# FPGA_Banks.net
KiCad netlist of a schematic drawn in Altium Designer
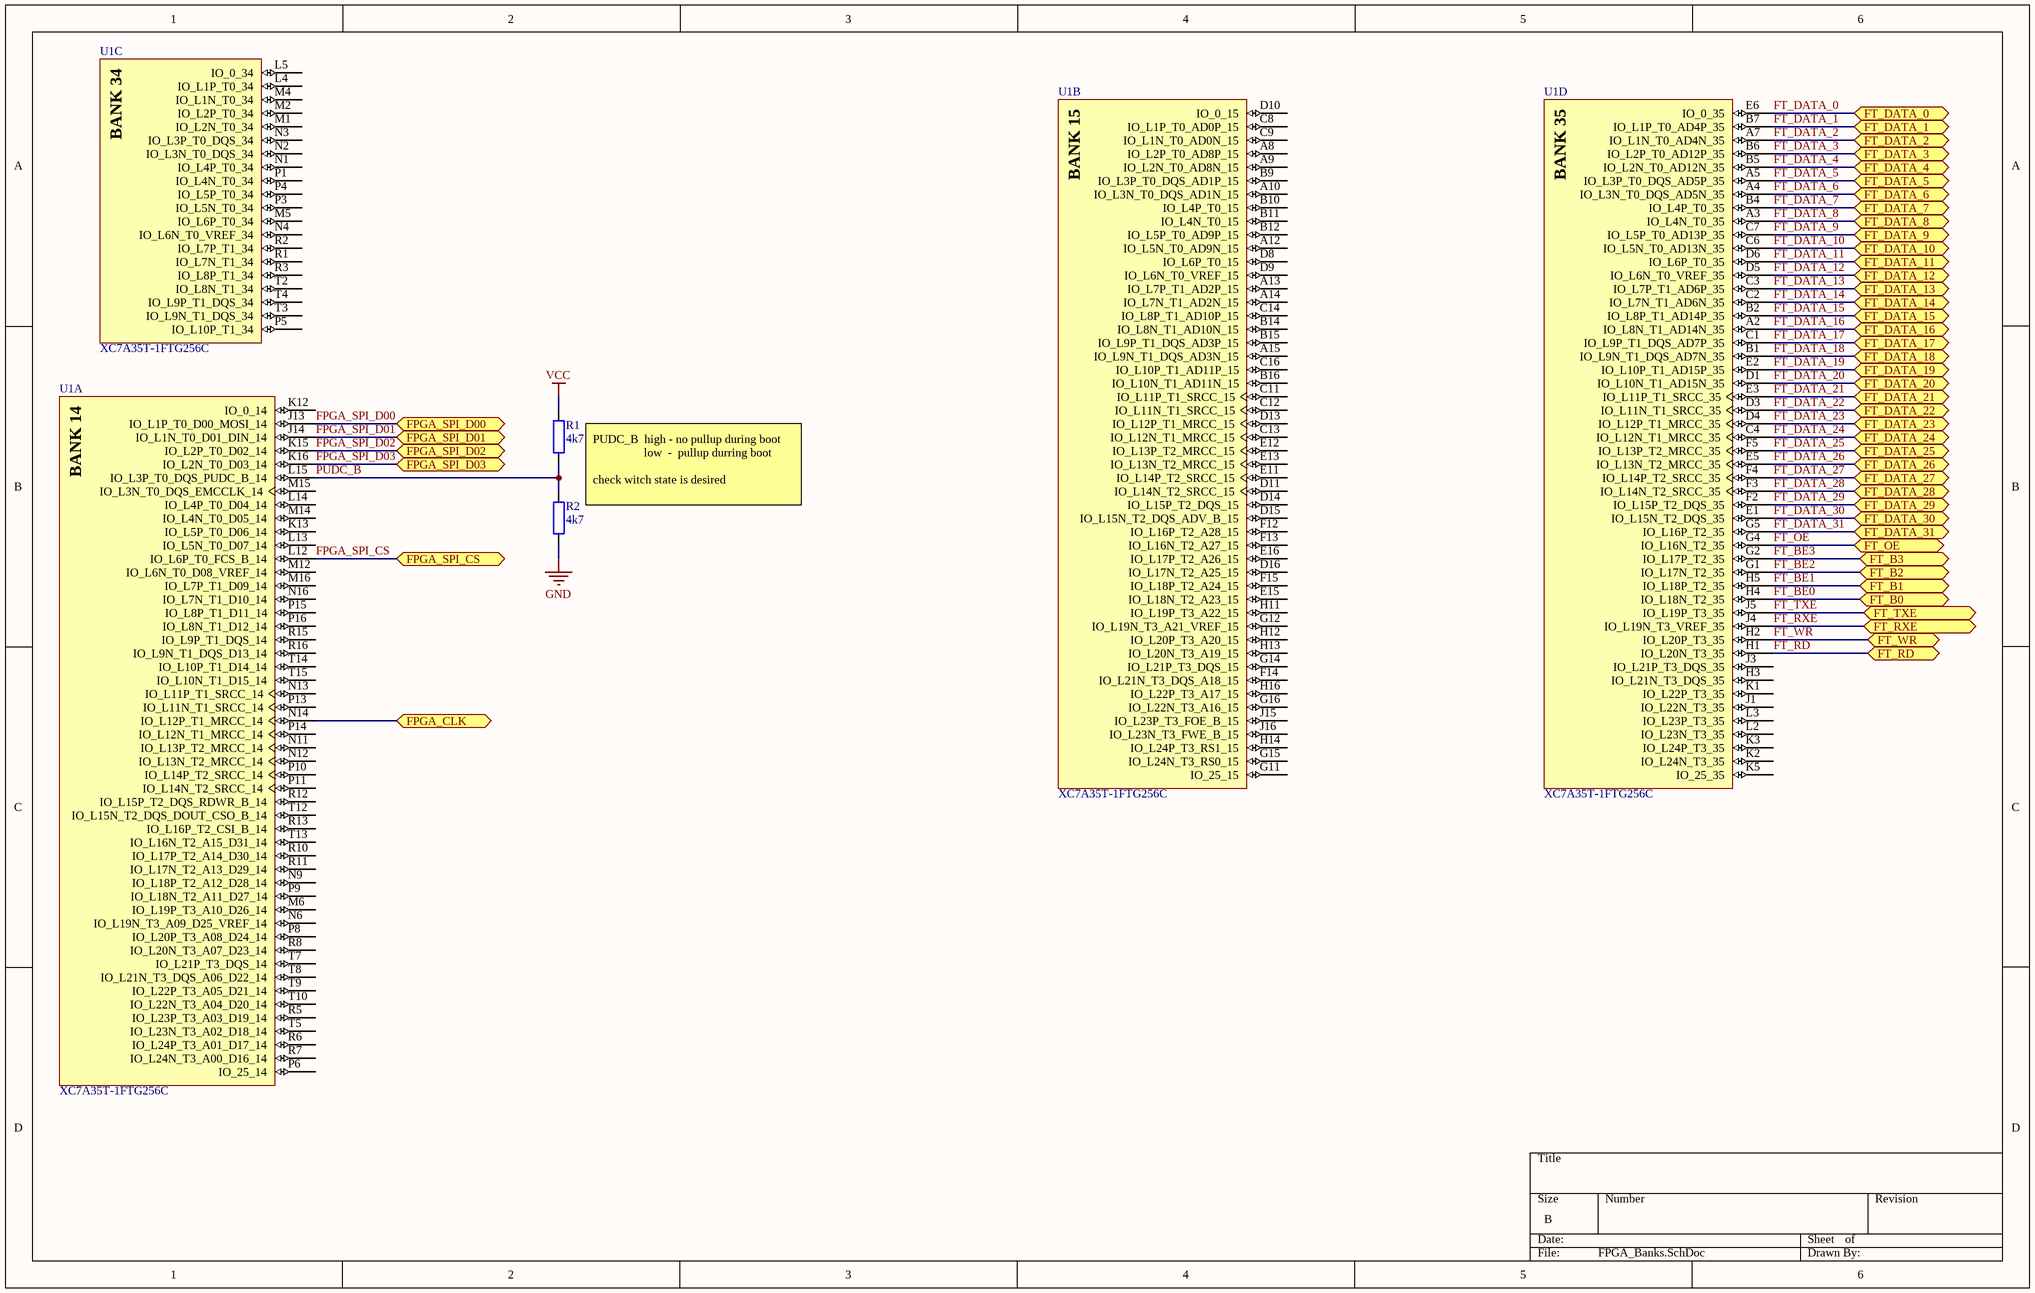
[diagram p0: FPGA_Banks.SchDoc]

(export (version "E")
  (design (tool "Eeschema 10.0.6"))
  (components
    (comp (ref "R1")
      (value "4k7")
      (footprint "RES0402")
      (libsource (lib "LimeMicroAltiumLib_schLib") (part "Res_0402"))
    )
    (comp (ref "R2")
      (value "4k7")
      (footprint "RES0402")
      (libsource (lib "LimeMicroAltiumLib_schLib") (part "Res_0402"))
    )
    (comp (ref "U1")
      (value "XC7A35T-1FTG256C")
      (footprint "FTG256")
      (description "Artix-7 FPGA, 170 User I/Os, 0 GTP, 256-Ball BGA, Speed Grade 1, Commercial Grade, Pb-Free")
      (fields (field (name "MANUFACTURER") "Xilinx"))
      (libsource (lib "Xilinx Artix-7") (part "XC7A35T-1FTG256C"))
    )
  )
  (nets
    (net (code "1") (name "/FPGA_CLK") (class "Default")
      (node (ref "U1") (pin "N14") (pinfunction "IO_L12P_T1_MRCC_14_N14") (pintype "bidirectional"))
    )
    (net (code "2") (name "/FPGA_SPI_CS") (class "Default")
      (node (ref "U1") (pin "L12") (pinfunction "IO_L6P_T0_FCS_B_14_L12") (pintype "bidirectional"))
    )
    (net (code "3") (name "/FPGA_SPI_D00") (class "Default")
      (node (ref "U1") (pin "J13") (pinfunction "IO_L1P_T0_D00_MOSI_14_J13") (pintype "bidirectional"))
    )
    (net (code "4") (name "/FPGA_SPI_D01") (class "Default")
      (node (ref "U1") (pin "J14") (pinfunction "IO_L1N_T0_D01_DIN_14_J14") (pintype "bidirectional"))
    )
    (net (code "5") (name "/FPGA_SPI_D02") (class "Default")
      (node (ref "U1") (pin "K15") (pinfunction "IO_L2P_T0_D02_14_K15") (pintype "bidirectional"))
    )
    (net (code "6") (name "/FPGA_SPI_D03") (class "Default")
      (node (ref "U1") (pin "K16") (pinfunction "IO_L2N_T0_D03_14_K16") (pintype "bidirectional"))
    )
    (net (code "7") (name "/FT_BE0") (class "Default")
      (node (ref "U1") (pin "H4") (pinfunction "IO_L18N_T2_35_H4") (pintype "bidirectional"))
    )
    (net (code "8") (name "/FT_BE1") (class "Default")
      (node (ref "U1") (pin "H5") (pinfunction "IO_L18P_T2_35_H5") (pintype "bidirectional"))
    )
    (net (code "9") (name "/FT_BE2") (class "Default")
      (node (ref "U1") (pin "G1") (pinfunction "IO_L17N_T2_35_G1") (pintype "bidirectional"))
    )
    (net (code "10") (name "/FT_BE3") (class "Default")
      (node (ref "U1") (pin "G2") (pinfunction "IO_L17P_T2_35_G2") (pintype "bidirectional"))
    )
    (net (code "11") (name "/FT_DATA_0") (class "Default")
      (node (ref "U1") (pin "E6") (pinfunction "IO_0_35_E6") (pintype "bidirectional"))
    )
    (net (code "12") (name "/FT_DATA_1") (class "Default")
      (node (ref "U1") (pin "B7") (pinfunction "IO_L1P_T0_AD4P_35_B7") (pintype "bidirectional"))
    )
    (net (code "13") (name "/FT_DATA_2") (class "Default")
      (node (ref "U1") (pin "A7") (pinfunction "IO_L1N_T0_AD4N_35_A7") (pintype "bidirectional"))
    )
    (net (code "14") (name "/FT_DATA_3") (class "Default")
      (node (ref "U1") (pin "B6") (pinfunction "IO_L2P_T0_AD12P_35_B6") (pintype "bidirectional"))
    )
    (net (code "15") (name "/FT_DATA_4") (class "Default")
      (node (ref "U1") (pin "B5") (pinfunction "IO_L2N_T0_AD12N_35_B5") (pintype "bidirectional"))
    )
    (net (code "16") (name "/FT_DATA_5") (class "Default")
      (node (ref "U1") (pin "A5") (pinfunction "IO_L3P_T0_DQS_AD5P_35_A5") (pintype "bidirectional"))
    )
    (net (code "17") (name "/FT_DATA_6") (class "Default")
      (node (ref "U1") (pin "A4") (pinfunction "IO_L3N_T0_DQS_AD5N_35_A4") (pintype "bidirectional"))
    )
    (net (code "18") (name "/FT_DATA_7") (class "Default")
      (node (ref "U1") (pin "B4") (pinfunction "IO_L4P_T0_35_B4") (pintype "bidirectional"))
    )
    (net (code "19") (name "/FT_DATA_8") (class "Default")
      (node (ref "U1") (pin "A3") (pinfunction "IO_L4N_T0_35_A3") (pintype "bidirectional"))
    )
    (net (code "20") (name "/FT_DATA_9") (class "Default")
      (node (ref "U1") (pin "C7") (pinfunction "IO_L5P_T0_AD13P_35_C7") (pintype "bidirectional"))
    )
    (net (code "21") (name "/FT_DATA_10") (class "Default")
      (node (ref "U1") (pin "C6") (pinfunction "IO_L5N_T0_AD13N_35_C6") (pintype "bidirectional"))
    )
    (net (code "22") (name "/FT_DATA_11") (class "Default")
      (node (ref "U1") (pin "D6") (pinfunction "IO_L6P_T0_35_D6") (pintype "bidirectional"))
    )
    (net (code "23") (name "/FT_DATA_12") (class "Default")
      (node (ref "U1") (pin "D5") (pinfunction "IO_L6N_T0_VREF_35_D5") (pintype "bidirectional"))
    )
    (net (code "24") (name "/FT_DATA_13") (class "Default")
      (node (ref "U1") (pin "C3") (pinfunction "IO_L7P_T1_AD6P_35_C3") (pintype "bidirectional"))
    )
    (net (code "25") (name "/FT_DATA_14") (class "Default")
      (node (ref "U1") (pin "C2") (pinfunction "IO_L7N_T1_AD6N_35_C2") (pintype "bidirectional"))
    )
    (net (code "26") (name "/FT_DATA_15") (class "Default")
      (node (ref "U1") (pin "B2") (pinfunction "IO_L8P_T1_AD14P_35_B2") (pintype "bidirectional"))
    )
    (net (code "27") (name "/FT_DATA_16") (class "Default")
      (node (ref "U1") (pin "A2") (pinfunction "IO_L8N_T1_AD14N_35_A2") (pintype "bidirectional"))
    )
    (net (code "28") (name "/FT_DATA_17") (class "Default")
      (node (ref "U1") (pin "C1") (pinfunction "IO_L9P_T1_DQS_AD7P_35_C1") (pintype "bidirectional"))
    )
    (net (code "29") (name "/FT_DATA_18") (class "Default")
      (node (ref "U1") (pin "B1") (pinfunction "IO_L9N_T1_DQS_AD7N_35_B1") (pintype "bidirectional"))
    )
    (net (code "30") (name "/FT_DATA_19") (class "Default")
      (node (ref "U1") (pin "E2") (pinfunction "IO_L10P_T1_AD15P_35_E2") (pintype "bidirectional"))
    )
    (net (code "31") (name "/FT_DATA_20") (class "Default")
      (node (ref "U1") (pin "D1") (pinfunction "IO_L10N_T1_AD15N_35_D1") (pintype "bidirectional"))
    )
    (net (code "32") (name "/FT_DATA_21") (class "Default")
      (node (ref "U1") (pin "E3") (pinfunction "IO_L11P_T1_SRCC_35_E3") (pintype "bidirectional"))
    )
    (net (code "33") (name "/FT_DATA_22") (class "Default")
      (node (ref "U1") (pin "D3") (pinfunction "IO_L11N_T1_SRCC_35_D3") (pintype "bidirectional"))
    )
    (net (code "34") (name "/FT_DATA_23") (class "Default")
      (node (ref "U1") (pin "D4") (pinfunction "IO_L12P_T1_MRCC_35_D4") (pintype "bidirectional"))
    )
    (net (code "35") (name "/FT_DATA_24") (class "Default")
      (node (ref "U1") (pin "C4") (pinfunction "IO_L12N_T1_MRCC_35_C4") (pintype "bidirectional"))
    )
    (net (code "36") (name "/FT_DATA_25") (class "Default")
      (node (ref "U1") (pin "F5") (pinfunction "IO_L13P_T2_MRCC_35_F5") (pintype "bidirectional"))
    )
    (net (code "37") (name "/FT_DATA_26") (class "Default")
      (node (ref "U1") (pin "E5") (pinfunction "IO_L13N_T2_MRCC_35_E5") (pintype "bidirectional"))
    )
    (net (code "38") (name "/FT_DATA_27") (class "Default")
      (node (ref "U1") (pin "F4") (pinfunction "IO_L14P_T2_SRCC_35_F4") (pintype "bidirectional"))
    )
    (net (code "39") (name "/FT_DATA_28") (class "Default")
      (node (ref "U1") (pin "F3") (pinfunction "IO_L14N_T2_SRCC_35_F3") (pintype "bidirectional"))
    )
    (net (code "40") (name "/FT_DATA_29") (class "Default")
      (node (ref "U1") (pin "F2") (pinfunction "IO_L15P_T2_DQS_35_F2") (pintype "bidirectional"))
    )
    (net (code "41") (name "/FT_DATA_30") (class "Default")
      (node (ref "U1") (pin "E1") (pinfunction "IO_L15N_T2_DQS_35_E1") (pintype "bidirectional"))
    )
    (net (code "42") (name "/FT_DATA_31") (class "Default")
      (node (ref "U1") (pin "G5") (pinfunction "IO_L16P_T2_35_G5") (pintype "bidirectional"))
    )
    (net (code "43") (name "/FT_OE") (class "Default")
      (node (ref "U1") (pin "G4") (pinfunction "IO_L16N_T2_35_G4") (pintype "bidirectional"))
    )
    (net (code "44") (name "/FT_RD") (class "Default")
      (node (ref "U1") (pin "H1") (pinfunction "IO_L20N_T3_35_H1") (pintype "bidirectional"))
    )
    (net (code "45") (name "/FT_RXE") (class "Default")
      (node (ref "U1") (pin "J4") (pinfunction "IO_L19N_T3_VREF_35_J4") (pintype "bidirectional"))
    )
    (net (code "46") (name "/FT_TXE") (class "Default")
      (node (ref "U1") (pin "J5") (pinfunction "IO_L19P_T3_35_J5") (pintype "bidirectional"))
    )
    (net (code "47") (name "/FT_WR") (class "Default")
      (node (ref "U1") (pin "H2") (pinfunction "IO_L20P_T3_35_H2") (pintype "bidirectional"))
    )
    (net (code "48") (name "/PUDC_B") (class "Default")
      (node (ref "R1") (pin "2") (pinfunction "2_2") (pintype "passive"))
      (node (ref "R2") (pin "1") (pinfunction "1_1") (pintype "passive"))
      (node (ref "U1") (pin "L15") (pinfunction "IO_L3P_T0_DQS_PUDC_B_14_L15") (pintype "bidirectional"))
    )
    (net (code "49") (name "GND") (class "Default")
      (node (ref "R2") (pin "2") (pinfunction "2_2") (pintype "passive"))
    )
    (net (code "50") (name "VCC") (class "Default")
      (node (ref "R1") (pin "1") (pinfunction "1_1") (pintype "passive"))
    )
    (net (code "51") (name "unconnected-(U1A-IO_0_14-PadK12)") (class "Default")
      (node (ref "U1") (pin "K12") (pinfunction "IO_0_14_K12") (pintype "bidirectional"))
    )
    (net (code "52") (name "unconnected-(U1A-IO_25_14-PadP6)") (class "Default")
      (node (ref "U1") (pin "P6") (pinfunction "IO_25_14_P6") (pintype "bidirectional"))
    )
    (net (code "53") (name "unconnected-(U1A-IO_L3N_T0_DQS_EMCCLK_14-PadM15)") (class "Default")
      (node (ref "U1") (pin "M15") (pinfunction "IO_L3N_T0_DQS_EMCCLK_14_M15") (pintype "bidirectional"))
    )
    (net (code "54") (name "unconnected-(U1A-IO_L4N_T0_D05_14-PadM14)") (class "Default")
      (node (ref "U1") (pin "M14") (pinfunction "IO_L4N_T0_D05_14_M14") (pintype "bidirectional"))
    )
    (net (code "55") (name "unconnected-(U1A-IO_L4P_T0_D04_14-PadL14)") (class "Default")
      (node (ref "U1") (pin "L14") (pinfunction "IO_L4P_T0_D04_14_L14") (pintype "bidirectional"))
    )
    (net (code "56") (name "unconnected-(U1A-IO_L5N_T0_D07_14-PadL13)") (class "Default")
      (node (ref "U1") (pin "L13") (pinfunction "IO_L5N_T0_D07_14_L13") (pintype "bidirectional"))
    )
    (net (code "57") (name "unconnected-(U1A-IO_L5P_T0_D06_14-PadK13)") (class "Default")
      (node (ref "U1") (pin "K13") (pinfunction "IO_L5P_T0_D06_14_K13") (pintype "bidirectional"))
    )
    (net (code "58") (name "unconnected-(U1A-IO_L6N_T0_D08_VREF_14-PadM12)") (class "Default")
      (node (ref "U1") (pin "M12") (pinfunction "IO_L6N_T0_D08_VREF_14_M12") (pintype "bidirectional"))
    )
    (net (code "59") (name "unconnected-(U1A-IO_L7N_T1_D10_14-PadN16)") (class "Default")
      (node (ref "U1") (pin "N16") (pinfunction "IO_L7N_T1_D10_14_N16") (pintype "bidirectional"))
    )
    (net (code "60") (name "unconnected-(U1A-IO_L7P_T1_D09_14-PadM16)") (class "Default")
      (node (ref "U1") (pin "M16") (pinfunction "IO_L7P_T1_D09_14_M16") (pintype "bidirectional"))
    )
    (net (code "61") (name "unconnected-(U1A-IO_L8N_T1_D12_14-PadP16)") (class "Default")
      (node (ref "U1") (pin "P16") (pinfunction "IO_L8N_T1_D12_14_P16") (pintype "bidirectional"))
    )
    (net (code "62") (name "unconnected-(U1A-IO_L8P_T1_D11_14-PadP15)") (class "Default")
      (node (ref "U1") (pin "P15") (pinfunction "IO_L8P_T1_D11_14_P15") (pintype "bidirectional"))
    )
    (net (code "63") (name "unconnected-(U1A-IO_L9N_T1_DQS_D13_14-PadR16)") (class "Default")
      (node (ref "U1") (pin "R16") (pinfunction "IO_L9N_T1_DQS_D13_14_R16") (pintype "bidirectional"))
    )
    (net (code "64") (name "unconnected-(U1A-IO_L9P_T1_DQS_14-PadR15)") (class "Default")
      (node (ref "U1") (pin "R15") (pinfunction "IO_L9P_T1_DQS_14_R15") (pintype "bidirectional"))
    )
    (net (code "65") (name "unconnected-(U1A-IO_L10N_T1_D15_14-PadT15)") (class "Default")
      (node (ref "U1") (pin "T15") (pinfunction "IO_L10N_T1_D15_14_T15") (pintype "bidirectional"))
    )
    (net (code "66") (name "unconnected-(U1A-IO_L10P_T1_D14_14-PadT14)") (class "Default")
      (node (ref "U1") (pin "T14") (pinfunction "IO_L10P_T1_D14_14_T14") (pintype "bidirectional"))
    )
    (net (code "67") (name "unconnected-(U1A-IO_L11N_T1_SRCC_14-PadP13)") (class "Default")
      (node (ref "U1") (pin "P13") (pinfunction "IO_L11N_T1_SRCC_14_P13") (pintype "bidirectional"))
    )
    (net (code "68") (name "unconnected-(U1A-IO_L11P_T1_SRCC_14-PadN13)") (class "Default")
      (node (ref "U1") (pin "N13") (pinfunction "IO_L11P_T1_SRCC_14_N13") (pintype "bidirectional"))
    )
    (net (code "69") (name "unconnected-(U1A-IO_L12N_T1_MRCC_14-PadP14)") (class "Default")
      (node (ref "U1") (pin "P14") (pinfunction "IO_L12N_T1_MRCC_14_P14") (pintype "bidirectional"))
    )
    (net (code "70") (name "unconnected-(U1A-IO_L13N_T2_MRCC_14-PadN12)") (class "Default")
      (node (ref "U1") (pin "N12") (pinfunction "IO_L13N_T2_MRCC_14_N12") (pintype "bidirectional"))
    )
    (net (code "71") (name "unconnected-(U1A-IO_L13P_T2_MRCC_14-PadN11)") (class "Default")
      (node (ref "U1") (pin "N11") (pinfunction "IO_L13P_T2_MRCC_14_N11") (pintype "bidirectional"))
    )
    (net (code "72") (name "unconnected-(U1A-IO_L14N_T2_SRCC_14-PadP11)") (class "Default")
      (node (ref "U1") (pin "P11") (pinfunction "IO_L14N_T2_SRCC_14_P11") (pintype "bidirectional"))
    )
    (net (code "73") (name "unconnected-(U1A-IO_L14P_T2_SRCC_14-PadP10)") (class "Default")
      (node (ref "U1") (pin "P10") (pinfunction "IO_L14P_T2_SRCC_14_P10") (pintype "bidirectional"))
    )
    (net (code "74") (name "unconnected-(U1A-IO_L15N_T2_DQS_DOUT_CSO_B_14-PadT12)") (class "Default")
      (node (ref "U1") (pin "T12") (pinfunction "IO_L15N_T2_DQS_DOUT_CSO_B_14_T12") (pintype "bidirectional"))
    )
    (net (code "75") (name "unconnected-(U1A-IO_L15P_T2_DQS_RDWR_B_14-PadR12)") (class "Default")
      (node (ref "U1") (pin "R12") (pinfunction "IO_L15P_T2_DQS_RDWR_B_14_R12") (pintype "bidirectional"))
    )
    (net (code "76") (name "unconnected-(U1A-IO_L16N_T2_A15_D31_14-PadT13)") (class "Default")
      (node (ref "U1") (pin "T13") (pinfunction "IO_L16N_T2_A15_D31_14_T13") (pintype "bidirectional"))
    )
    (net (code "77") (name "unconnected-(U1A-IO_L16P_T2_CSI_B_14-PadR13)") (class "Default")
      (node (ref "U1") (pin "R13") (pinfunction "IO_L16P_T2_CSI_B_14_R13") (pintype "bidirectional"))
    )
    (net (code "78") (name "unconnected-(U1A-IO_L17N_T2_A13_D29_14-PadR11)") (class "Default")
      (node (ref "U1") (pin "R11") (pinfunction "IO_L17N_T2_A13_D29_14_R11") (pintype "bidirectional"))
    )
    (net (code "79") (name "unconnected-(U1A-IO_L17P_T2_A14_D30_14-PadR10)") (class "Default")
      (node (ref "U1") (pin "R10") (pinfunction "IO_L17P_T2_A14_D30_14_R10") (pintype "bidirectional"))
    )
    (net (code "80") (name "unconnected-(U1A-IO_L18N_T2_A11_D27_14-PadP9)") (class "Default")
      (node (ref "U1") (pin "P9") (pinfunction "IO_L18N_T2_A11_D27_14_P9") (pintype "bidirectional"))
    )
    (net (code "81") (name "unconnected-(U1A-IO_L18P_T2_A12_D28_14-PadN9)") (class "Default")
      (node (ref "U1") (pin "N9") (pinfunction "IO_L18P_T2_A12_D28_14_N9") (pintype "bidirectional"))
    )
    (net (code "82") (name "unconnected-(U1A-IO_L19N_T3_A09_D25_VREF_14-PadN6)") (class "Default")
      (node (ref "U1") (pin "N6") (pinfunction "IO_L19N_T3_A09_D25_VREF_14_N6") (pintype "bidirectional"))
    )
    (net (code "83") (name "unconnected-(U1A-IO_L19P_T3_A10_D26_14-PadM6)") (class "Default")
      (node (ref "U1") (pin "M6") (pinfunction "IO_L19P_T3_A10_D26_14_M6") (pintype "bidirectional"))
    )
    (net (code "84") (name "unconnected-(U1A-IO_L20N_T3_A07_D23_14-PadR8)") (class "Default")
      (node (ref "U1") (pin "R8") (pinfunction "IO_L20N_T3_A07_D23_14_R8") (pintype "bidirectional"))
    )
    (net (code "85") (name "unconnected-(U1A-IO_L20P_T3_A08_D24_14-PadP8)") (class "Default")
      (node (ref "U1") (pin "P8") (pinfunction "IO_L20P_T3_A08_D24_14_P8") (pintype "bidirectional"))
    )
    (net (code "86") (name "unconnected-(U1A-IO_L21N_T3_DQS_A06_D22_14-PadT8)") (class "Default")
      (node (ref "U1") (pin "T8") (pinfunction "IO_L21N_T3_DQS_A06_D22_14_T8") (pintype "bidirectional"))
    )
    (net (code "87") (name "unconnected-(U1A-IO_L21P_T3_DQS_14-PadT7)") (class "Default")
      (node (ref "U1") (pin "T7") (pinfunction "IO_L21P_T3_DQS_14_T7") (pintype "bidirectional"))
    )
    (net (code "88") (name "unconnected-(U1A-IO_L22N_T3_A04_D20_14-PadT10)") (class "Default")
      (node (ref "U1") (pin "T10") (pinfunction "IO_L22N_T3_A04_D20_14_T10") (pintype "bidirectional"))
    )
    (net (code "89") (name "unconnected-(U1A-IO_L22P_T3_A05_D21_14-PadT9)") (class "Default")
      (node (ref "U1") (pin "T9") (pinfunction "IO_L22P_T3_A05_D21_14_T9") (pintype "bidirectional"))
    )
    (net (code "90") (name "unconnected-(U1A-IO_L23N_T3_A02_D18_14-PadT5)") (class "Default")
      (node (ref "U1") (pin "T5") (pinfunction "IO_L23N_T3_A02_D18_14_T5") (pintype "bidirectional"))
    )
    (net (code "91") (name "unconnected-(U1A-IO_L23P_T3_A03_D19_14-PadR5)") (class "Default")
      (node (ref "U1") (pin "R5") (pinfunction "IO_L23P_T3_A03_D19_14_R5") (pintype "bidirectional"))
    )
    (net (code "92") (name "unconnected-(U1A-IO_L24N_T3_A00_D16_14-PadR7)") (class "Default")
      (node (ref "U1") (pin "R7") (pinfunction "IO_L24N_T3_A00_D16_14_R7") (pintype "bidirectional"))
    )
    (net (code "93") (name "unconnected-(U1A-IO_L24P_T3_A01_D17_14-PadR6)") (class "Default")
      (node (ref "U1") (pin "R6") (pinfunction "IO_L24P_T3_A01_D17_14_R6") (pintype "bidirectional"))
    )
    (net (code "94") (name "unconnected-(U1B-IO_0_15-PadD10)") (class "Default")
      (node (ref "U1") (pin "D10") (pinfunction "IO_0_15_D10") (pintype "bidirectional"))
    )
    (net (code "95") (name "unconnected-(U1B-IO_25_15-PadG11)") (class "Default")
      (node (ref "U1") (pin "G11") (pinfunction "IO_25_15_G11") (pintype "bidirectional"))
    )
    (net (code "96") (name "unconnected-(U1B-IO_L1N_T0_AD0N_15-PadC9)") (class "Default")
      (node (ref "U1") (pin "C9") (pinfunction "IO_L1N_T0_AD0N_15_C9") (pintype "bidirectional"))
    )
    (net (code "97") (name "unconnected-(U1B-IO_L1P_T0_AD0P_15-PadC8)") (class "Default")
      (node (ref "U1") (pin "C8") (pinfunction "IO_L1P_T0_AD0P_15_C8") (pintype "bidirectional"))
    )
    (net (code "98") (name "unconnected-(U1B-IO_L2N_T0_AD8N_15-PadA9)") (class "Default")
      (node (ref "U1") (pin "A9") (pinfunction "IO_L2N_T0_AD8N_15_A9") (pintype "bidirectional"))
    )
    (net (code "99") (name "unconnected-(U1B-IO_L2P_T0_AD8P_15-PadA8)") (class "Default")
      (node (ref "U1") (pin "A8") (pinfunction "IO_L2P_T0_AD8P_15_A8") (pintype "bidirectional"))
    )
    (net (code "100") (name "unconnected-(U1B-IO_L3N_T0_DQS_AD1N_15-PadA10)") (class "Default")
      (node (ref "U1") (pin "A10") (pinfunction "IO_L3N_T0_DQS_AD1N_15_A10") (pintype "bidirectional"))
    )
    (net (code "101") (name "unconnected-(U1B-IO_L3P_T0_DQS_AD1P_15-PadB9)") (class "Default")
      (node (ref "U1") (pin "B9") (pinfunction "IO_L3P_T0_DQS_AD1P_15_B9") (pintype "bidirectional"))
    )
    (net (code "102") (name "unconnected-(U1B-IO_L4N_T0_15-PadB11)") (class "Default")
      (node (ref "U1") (pin "B11") (pinfunction "IO_L4N_T0_15_B11") (pintype "bidirectional"))
    )
    (net (code "103") (name "unconnected-(U1B-IO_L4P_T0_15-PadB10)") (class "Default")
      (node (ref "U1") (pin "B10") (pinfunction "IO_L4P_T0_15_B10") (pintype "bidirectional"))
    )
    (net (code "104") (name "unconnected-(U1B-IO_L5N_T0_AD9N_15-PadA12)") (class "Default")
      (node (ref "U1") (pin "A12") (pinfunction "IO_L5N_T0_AD9N_15_A12") (pintype "bidirectional"))
    )
    (net (code "105") (name "unconnected-(U1B-IO_L5P_T0_AD9P_15-PadB12)") (class "Default")
      (node (ref "U1") (pin "B12") (pinfunction "IO_L5P_T0_AD9P_15_B12") (pintype "bidirectional"))
    )
    (net (code "106") (name "unconnected-(U1B-IO_L6N_T0_VREF_15-PadD9)") (class "Default")
      (node (ref "U1") (pin "D9") (pinfunction "IO_L6N_T0_VREF_15_D9") (pintype "bidirectional"))
    )
    (net (code "107") (name "unconnected-(U1B-IO_L6P_T0_15-PadD8)") (class "Default")
      (node (ref "U1") (pin "D8") (pinfunction "IO_L6P_T0_15_D8") (pintype "bidirectional"))
    )
    (net (code "108") (name "unconnected-(U1B-IO_L7N_T1_AD2N_15-PadA14)") (class "Default")
      (node (ref "U1") (pin "A14") (pinfunction "IO_L7N_T1_AD2N_15_A14") (pintype "bidirectional"))
    )
    (net (code "109") (name "unconnected-(U1B-IO_L7P_T1_AD2P_15-PadA13)") (class "Default")
      (node (ref "U1") (pin "A13") (pinfunction "IO_L7P_T1_AD2P_15_A13") (pintype "bidirectional"))
    )
    (net (code "110") (name "unconnected-(U1B-IO_L8N_T1_AD10N_15-PadB14)") (class "Default")
      (node (ref "U1") (pin "B14") (pinfunction "IO_L8N_T1_AD10N_15_B14") (pintype "bidirectional"))
    )
    (net (code "111") (name "unconnected-(U1B-IO_L8P_T1_AD10P_15-PadC14)") (class "Default")
      (node (ref "U1") (pin "C14") (pinfunction "IO_L8P_T1_AD10P_15_C14") (pintype "bidirectional"))
    )
    (net (code "112") (name "unconnected-(U1B-IO_L9N_T1_DQS_AD3N_15-PadA15)") (class "Default")
      (node (ref "U1") (pin "A15") (pinfunction "IO_L9N_T1_DQS_AD3N_15_A15") (pintype "bidirectional"))
    )
    (net (code "113") (name "unconnected-(U1B-IO_L9P_T1_DQS_AD3P_15-PadB15)") (class "Default")
      (node (ref "U1") (pin "B15") (pinfunction "IO_L9P_T1_DQS_AD3P_15_B15") (pintype "bidirectional"))
    )
    (net (code "114") (name "unconnected-(U1B-IO_L10N_T1_AD11N_15-PadB16)") (class "Default")
      (node (ref "U1") (pin "B16") (pinfunction "IO_L10N_T1_AD11N_15_B16") (pintype "bidirectional"))
    )
    (net (code "115") (name "unconnected-(U1B-IO_L10P_T1_AD11P_15-PadC16)") (class "Default")
      (node (ref "U1") (pin "C16") (pinfunction "IO_L10P_T1_AD11P_15_C16") (pintype "bidirectional"))
    )
    (net (code "116") (name "unconnected-(U1B-IO_L11N_T1_SRCC_15-PadC12)") (class "Default")
      (node (ref "U1") (pin "C12") (pinfunction "IO_L11N_T1_SRCC_15_C12") (pintype "bidirectional"))
    )
    (net (code "117") (name "unconnected-(U1B-IO_L11P_T1_SRCC_15-PadC11)") (class "Default")
      (node (ref "U1") (pin "C11") (pinfunction "IO_L11P_T1_SRCC_15_C11") (pintype "bidirectional"))
    )
    (net (code "118") (name "unconnected-(U1B-IO_L12N_T1_MRCC_15-PadC13)") (class "Default")
      (node (ref "U1") (pin "C13") (pinfunction "IO_L12N_T1_MRCC_15_C13") (pintype "bidirectional"))
    )
    (net (code "119") (name "unconnected-(U1B-IO_L12P_T1_MRCC_15-PadD13)") (class "Default")
      (node (ref "U1") (pin "D13") (pinfunction "IO_L12P_T1_MRCC_15_D13") (pintype "bidirectional"))
    )
    (net (code "120") (name "unconnected-(U1B-IO_L13N_T2_MRCC_15-PadE13)") (class "Default")
      (node (ref "U1") (pin "E13") (pinfunction "IO_L13N_T2_MRCC_15_E13") (pintype "bidirectional"))
    )
    (net (code "121") (name "unconnected-(U1B-IO_L13P_T2_MRCC_15-PadE12)") (class "Default")
      (node (ref "U1") (pin "E12") (pinfunction "IO_L13P_T2_MRCC_15_E12") (pintype "bidirectional"))
    )
    (net (code "122") (name "unconnected-(U1B-IO_L14N_T2_SRCC_15-PadD11)") (class "Default")
      (node (ref "U1") (pin "D11") (pinfunction "IO_L14N_T2_SRCC_15_D11") (pintype "bidirectional"))
    )
    (net (code "123") (name "unconnected-(U1B-IO_L14P_T2_SRCC_15-PadE11)") (class "Default")
      (node (ref "U1") (pin "E11") (pinfunction "IO_L14P_T2_SRCC_15_E11") (pintype "bidirectional"))
    )
    (net (code "124") (name "unconnected-(U1B-IO_L15N_T2_DQS_ADV_B_15-PadD15)") (class "Default")
      (node (ref "U1") (pin "D15") (pinfunction "IO_L15N_T2_DQS_ADV_B_15_D15") (pintype "bidirectional"))
    )
    (net (code "125") (name "unconnected-(U1B-IO_L15P_T2_DQS_15-PadD14)") (class "Default")
      (node (ref "U1") (pin "D14") (pinfunction "IO_L15P_T2_DQS_15_D14") (pintype "bidirectional"))
    )
    (net (code "126") (name "unconnected-(U1B-IO_L16N_T2_A27_15-PadF13)") (class "Default")
      (node (ref "U1") (pin "F13") (pinfunction "IO_L16N_T2_A27_15_F13") (pintype "bidirectional"))
    )
    (net (code "127") (name "unconnected-(U1B-IO_L16P_T2_A28_15-PadF12)") (class "Default")
      (node (ref "U1") (pin "F12") (pinfunction "IO_L16P_T2_A28_15_F12") (pintype "bidirectional"))
    )
    (net (code "128") (name "unconnected-(U1B-IO_L17N_T2_A25_15-PadD16)") (class "Default")
      (node (ref "U1") (pin "D16") (pinfunction "IO_L17N_T2_A25_15_D16") (pintype "bidirectional"))
    )
    (net (code "129") (name "unconnected-(U1B-IO_L17P_T2_A26_15-PadE16)") (class "Default")
      (node (ref "U1") (pin "E16") (pinfunction "IO_L17P_T2_A26_15_E16") (pintype "bidirectional"))
    )
    (net (code "130") (name "unconnected-(U1B-IO_L18N_T2_A23_15-PadE15)") (class "Default")
      (node (ref "U1") (pin "E15") (pinfunction "IO_L18N_T2_A23_15_E15") (pintype "bidirectional"))
    )
    (net (code "131") (name "unconnected-(U1B-IO_L18P_T2_A24_15-PadF15)") (class "Default")
      (node (ref "U1") (pin "F15") (pinfunction "IO_L18P_T2_A24_15_F15") (pintype "bidirectional"))
    )
    (net (code "132") (name "unconnected-(U1B-IO_L19N_T3_A21_VREF_15-PadG12)") (class "Default")
      (node (ref "U1") (pin "G12") (pinfunction "IO_L19N_T3_A21_VREF_15_G12") (pintype "bidirectional"))
    )
    (net (code "133") (name "unconnected-(U1B-IO_L19P_T3_A22_15-PadH11)") (class "Default")
      (node (ref "U1") (pin "H11") (pinfunction "IO_L19P_T3_A22_15_H11") (pintype "bidirectional"))
    )
    (net (code "134") (name "unconnected-(U1B-IO_L20N_T3_A19_15-PadH13)") (class "Default")
      (node (ref "U1") (pin "H13") (pinfunction "IO_L20N_T3_A19_15_H13") (pintype "bidirectional"))
    )
    (net (code "135") (name "unconnected-(U1B-IO_L20P_T3_A20_15-PadH12)") (class "Default")
      (node (ref "U1") (pin "H12") (pinfunction "IO_L20P_T3_A20_15_H12") (pintype "bidirectional"))
    )
    (net (code "136") (name "unconnected-(U1B-IO_L21N_T3_DQS_A18_15-PadF14)") (class "Default")
      (node (ref "U1") (pin "F14") (pinfunction "IO_L21N_T3_DQS_A18_15_F14") (pintype "bidirectional"))
    )
    (net (code "137") (name "unconnected-(U1B-IO_L21P_T3_DQS_15-PadG14)") (class "Default")
      (node (ref "U1") (pin "G14") (pinfunction "IO_L21P_T3_DQS_15_G14") (pintype "bidirectional"))
    )
    (net (code "138") (name "unconnected-(U1B-IO_L22N_T3_A16_15-PadG16)") (class "Default")
      (node (ref "U1") (pin "G16") (pinfunction "IO_L22N_T3_A16_15_G16") (pintype "bidirectional"))
    )
    (net (code "139") (name "unconnected-(U1B-IO_L22P_T3_A17_15-PadH16)") (class "Default")
      (node (ref "U1") (pin "H16") (pinfunction "IO_L22P_T3_A17_15_H16") (pintype "bidirectional"))
    )
    (net (code "140") (name "unconnected-(U1B-IO_L23N_T3_FWE_B_15-PadJ16)") (class "Default")
      (node (ref "U1") (pin "J16") (pinfunction "IO_L23N_T3_FWE_B_15_J16") (pintype "bidirectional"))
    )
    (net (code "141") (name "unconnected-(U1B-IO_L23P_T3_FOE_B_15-PadJ15)") (class "Default")
      (node (ref "U1") (pin "J15") (pinfunction "IO_L23P_T3_FOE_B_15_J15") (pintype "bidirectional"))
    )
    (net (code "142") (name "unconnected-(U1B-IO_L24N_T3_RS0_15-PadG15)") (class "Default")
      (node (ref "U1") (pin "G15") (pinfunction "IO_L24N_T3_RS0_15_G15") (pintype "bidirectional"))
    )
    (net (code "143") (name "unconnected-(U1B-IO_L24P_T3_RS1_15-PadH14)") (class "Default")
      (node (ref "U1") (pin "H14") (pinfunction "IO_L24P_T3_RS1_15_H14") (pintype "bidirectional"))
    )
    (net (code "144") (name "unconnected-(U1C-IO_0_34-PadL5)") (class "Default")
      (node (ref "U1") (pin "L5") (pinfunction "IO_0_34_L5") (pintype "bidirectional"))
    )
    (net (code "145") (name "unconnected-(U1C-IO_L1N_T0_34-PadM4)") (class "Default")
      (node (ref "U1") (pin "M4") (pinfunction "IO_L1N_T0_34_M4") (pintype "bidirectional"))
    )
    (net (code "146") (name "unconnected-(U1C-IO_L1P_T0_34-PadL4)") (class "Default")
      (node (ref "U1") (pin "L4") (pinfunction "IO_L1P_T0_34_L4") (pintype "bidirectional"))
    )
    (net (code "147") (name "unconnected-(U1C-IO_L2N_T0_34-PadM1)") (class "Default")
      (node (ref "U1") (pin "M1") (pinfunction "IO_L2N_T0_34_M1") (pintype "bidirectional"))
    )
    (net (code "148") (name "unconnected-(U1C-IO_L2P_T0_34-PadM2)") (class "Default")
      (node (ref "U1") (pin "M2") (pinfunction "IO_L2P_T0_34_M2") (pintype "bidirectional"))
    )
    (net (code "149") (name "unconnected-(U1C-IO_L3N_T0_DQS_34-PadN2)") (class "Default")
      (node (ref "U1") (pin "N2") (pinfunction "IO_L3N_T0_DQS_34_N2") (pintype "bidirectional"))
    )
    (net (code "150") (name "unconnected-(U1C-IO_L3P_T0_DQS_34-PadN3)") (class "Default")
      (node (ref "U1") (pin "N3") (pinfunction "IO_L3P_T0_DQS_34_N3") (pintype "bidirectional"))
    )
    (net (code "151") (name "unconnected-(U1C-IO_L4N_T0_34-PadP1)") (class "Default")
      (node (ref "U1") (pin "P1") (pinfunction "IO_L4N_T0_34_P1") (pintype "bidirectional"))
    )
    (net (code "152") (name "unconnected-(U1C-IO_L4P_T0_34-PadN1)") (class "Default")
      (node (ref "U1") (pin "N1") (pinfunction "IO_L4P_T0_34_N1") (pintype "bidirectional"))
    )
    (net (code "153") (name "unconnected-(U1C-IO_L5N_T0_34-PadP3)") (class "Default")
      (node (ref "U1") (pin "P3") (pinfunction "IO_L5N_T0_34_P3") (pintype "bidirectional"))
    )
    (net (code "154") (name "unconnected-(U1C-IO_L5P_T0_34-PadP4)") (class "Default")
      (node (ref "U1") (pin "P4") (pinfunction "IO_L5P_T0_34_P4") (pintype "bidirectional"))
    )
    (net (code "155") (name "unconnected-(U1C-IO_L6N_T0_VREF_34-PadN4)") (class "Default")
      (node (ref "U1") (pin "N4") (pinfunction "IO_L6N_T0_VREF_34_N4") (pintype "bidirectional"))
    )
    (net (code "156") (name "unconnected-(U1C-IO_L6P_T0_34-PadM5)") (class "Default")
      (node (ref "U1") (pin "M5") (pinfunction "IO_L6P_T0_34_M5") (pintype "bidirectional"))
    )
    (net (code "157") (name "unconnected-(U1C-IO_L7N_T1_34-PadR1)") (class "Default")
      (node (ref "U1") (pin "R1") (pinfunction "IO_L7N_T1_34_R1") (pintype "bidirectional"))
    )
    (net (code "158") (name "unconnected-(U1C-IO_L7P_T1_34-PadR2)") (class "Default")
      (node (ref "U1") (pin "R2") (pinfunction "IO_L7P_T1_34_R2") (pintype "bidirectional"))
    )
    (net (code "159") (name "unconnected-(U1C-IO_L8N_T1_34-PadT2)") (class "Default")
      (node (ref "U1") (pin "T2") (pinfunction "IO_L8N_T1_34_T2") (pintype "bidirectional"))
    )
    (net (code "160") (name "unconnected-(U1C-IO_L8P_T1_34-PadR3)") (class "Default")
      (node (ref "U1") (pin "R3") (pinfunction "IO_L8P_T1_34_R3") (pintype "bidirectional"))
    )
    (net (code "161") (name "unconnected-(U1C-IO_L9N_T1_DQS_34-PadT3)") (class "Default")
      (node (ref "U1") (pin "T3") (pinfunction "IO_L9N_T1_DQS_34_T3") (pintype "bidirectional"))
    )
    (net (code "162") (name "unconnected-(U1C-IO_L9P_T1_DQS_34-PadT4)") (class "Default")
      (node (ref "U1") (pin "T4") (pinfunction "IO_L9P_T1_DQS_34_T4") (pintype "bidirectional"))
    )
    (net (code "163") (name "unconnected-(U1C-IO_L10P_T1_34-PadP5)") (class "Default")
      (node (ref "U1") (pin "P5") (pinfunction "IO_L10P_T1_34_P5") (pintype "bidirectional"))
    )
    (net (code "164") (name "unconnected-(U1D-IO_25_35-PadK5)") (class "Default")
      (node (ref "U1") (pin "K5") (pinfunction "IO_25_35_K5") (pintype "bidirectional"))
    )
    (net (code "165") (name "unconnected-(U1D-IO_L21N_T3_DQS_35-PadH3)") (class "Default")
      (node (ref "U1") (pin "H3") (pinfunction "IO_L21N_T3_DQS_35_H3") (pintype "bidirectional"))
    )
    (net (code "166") (name "unconnected-(U1D-IO_L21P_T3_DQS_35-PadJ3)") (class "Default")
      (node (ref "U1") (pin "J3") (pinfunction "IO_L21P_T3_DQS_35_J3") (pintype "bidirectional"))
    )
    (net (code "167") (name "unconnected-(U1D-IO_L22N_T3_35-PadJ1)") (class "Default")
      (node (ref "U1") (pin "J1") (pinfunction "IO_L22N_T3_35_J1") (pintype "bidirectional"))
    )
    (net (code "168") (name "unconnected-(U1D-IO_L22P_T3_35-PadK1)") (class "Default")
      (node (ref "U1") (pin "K1") (pinfunction "IO_L22P_T3_35_K1") (pintype "bidirectional"))
    )
    (net (code "169") (name "unconnected-(U1D-IO_L23N_T3_35-PadL2)") (class "Default")
      (node (ref "U1") (pin "L2") (pinfunction "IO_L23N_T3_35_L2") (pintype "bidirectional"))
    )
    (net (code "170") (name "unconnected-(U1D-IO_L23P_T3_35-PadL3)") (class "Default")
      (node (ref "U1") (pin "L3") (pinfunction "IO_L23P_T3_35_L3") (pintype "bidirectional"))
    )
    (net (code "171") (name "unconnected-(U1D-IO_L24N_T3_35-PadK2)") (class "Default")
      (node (ref "U1") (pin "K2") (pinfunction "IO_L24N_T3_35_K2") (pintype "bidirectional"))
    )
    (net (code "172") (name "unconnected-(U1D-IO_L24P_T3_35-PadK3)") (class "Default")
      (node (ref "U1") (pin "K3") (pinfunction "IO_L24P_T3_35_K3") (pintype "bidirectional"))
    )
  )
)
